# Arc.net
KiCad netlist of a schematic drawn in Altium Designer
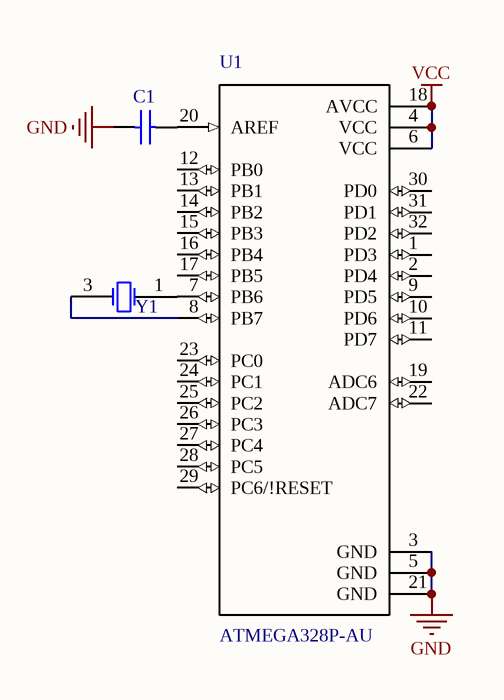
[diagram p0: Arc.SchDoc]

(export (version "E")
  (design (tool "Eeschema 10.0.6"))
  (components
    (comp (ref "C1")
      (value "100nF (104) 10% 16V")
      (footprint "0402_C")
      (description "贴片电容")
      (libsource (lib "Miscellaneous Devices LC") (part "0402 100nF (104) 10% 16V"))
    )
    (comp (ref "U1")
      (value "ATMEGA328P-AU")
      (footprint "*QFP80P900X900X120-32N")
      (description "Microcontroller Mcu, 8 Bit, Atmega, 20mhz, Tqfp-32")
      (fields (field (name "MF") "Microchip"))
      (libsource (lib "altium-import") (part "root_0_ATMEGA328P-AU_"))
    )
    (comp (ref "Y1")
      (value "16MHZ 9PF 10PPM")
      (footprint "SMD-3225_4P")
      (description "贴片晶振")
      (libsource (lib "Miscellaneous Devices LC") (part "SMD-3225_4P  16MHZ 9PF 10PPM"))
    )
  )
  (nets
    (net (code "1") (name "GND") (class "Default")
      (node (ref "C1") (pin "1") (pinfunction "1_1") (pintype "passive"))
      (node (ref "U1") (pin "21") (pinfunction "GND_21") (pintype "power_in"))
      (node (ref "U1") (pin "3") (pinfunction "GND_3") (pintype "power_in"))
      (node (ref "U1") (pin "5") (pinfunction "GND_5") (pintype "power_in"))
    )
    (net (code "2") (name "Net-(U1-AREF)") (class "Default")
      (node (ref "C1") (pin "2") (pinfunction "2_2") (pintype "passive"))
      (node (ref "U1") (pin "20") (pinfunction "AREF_20") (pintype "input"))
    )
    (net (code "3") (name "Net-(U1-PB6)") (class "Default")
      (node (ref "U1") (pin "7") (pinfunction "PB6_7") (pintype "bidirectional"))
      (node (ref "Y1") (pin "1") (pinfunction "OSC1_1") (pintype "passive"))
    )
    (net (code "4") (name "Net-(U1-PB7)") (class "Default")
      (node (ref "U1") (pin "8") (pinfunction "PB7_8") (pintype "bidirectional"))
      (node (ref "Y1") (pin "3") (pinfunction "OSC2_3") (pintype "passive"))
    )
    (net (code "5") (name "VCC") (class "Default")
      (node (ref "U1") (pin "18") (pinfunction "AVCC_18") (pintype "power_in"))
      (node (ref "U1") (pin "4") (pinfunction "VCC_4") (pintype "power_in"))
      (node (ref "U1") (pin "6") (pinfunction "VCC_6") (pintype "power_in"))
    )
    (net (code "6") (name "unconnected-(U1-ADC6-Pad19)") (class "Default")
      (node (ref "U1") (pin "19") (pinfunction "ADC6_19") (pintype "bidirectional"))
    )
    (net (code "7") (name "unconnected-(U1-ADC7-Pad22)") (class "Default")
      (node (ref "U1") (pin "22") (pinfunction "ADC7_22") (pintype "bidirectional"))
    )
    (net (code "8") (name "unconnected-(U1-PB0-Pad12)") (class "Default")
      (node (ref "U1") (pin "12") (pinfunction "PB0_12") (pintype "bidirectional"))
    )
    (net (code "9") (name "unconnected-(U1-PB1-Pad13)") (class "Default")
      (node (ref "U1") (pin "13") (pinfunction "PB1_13") (pintype "bidirectional"))
    )
    (net (code "10") (name "unconnected-(U1-PB2-Pad14)") (class "Default")
      (node (ref "U1") (pin "14") (pinfunction "PB2_14") (pintype "bidirectional"))
    )
    (net (code "11") (name "unconnected-(U1-PB3-Pad15)") (class "Default")
      (node (ref "U1") (pin "15") (pinfunction "PB3_15") (pintype "bidirectional"))
    )
    (net (code "12") (name "unconnected-(U1-PB4-Pad16)") (class "Default")
      (node (ref "U1") (pin "16") (pinfunction "PB4_16") (pintype "bidirectional"))
    )
    (net (code "13") (name "unconnected-(U1-PB5-Pad17)") (class "Default")
      (node (ref "U1") (pin "17") (pinfunction "PB5_17") (pintype "bidirectional"))
    )
    (net (code "14") (name "unconnected-(U1-PC0-Pad23)") (class "Default")
      (node (ref "U1") (pin "23") (pinfunction "PC0_23") (pintype "bidirectional"))
    )
    (net (code "15") (name "unconnected-(U1-PC1-Pad24)") (class "Default")
      (node (ref "U1") (pin "24") (pinfunction "PC1_24") (pintype "bidirectional"))
    )
    (net (code "16") (name "unconnected-(U1-PC2-Pad25)") (class "Default")
      (node (ref "U1") (pin "25") (pinfunction "PC2_25") (pintype "bidirectional"))
    )
    (net (code "17") (name "unconnected-(U1-PC3-Pad26)") (class "Default")
      (node (ref "U1") (pin "26") (pinfunction "PC3_26") (pintype "bidirectional"))
    )
    (net (code "18") (name "unconnected-(U1-PC4-Pad27)") (class "Default")
      (node (ref "U1") (pin "27") (pinfunction "PC4_27") (pintype "bidirectional"))
    )
    (net (code "19") (name "unconnected-(U1-PC5-Pad28)") (class "Default")
      (node (ref "U1") (pin "28") (pinfunction "PC5_28") (pintype "bidirectional"))
    )
    (net (code "20") (name "unconnected-(U1-PC6{slash}!RESET-Pad29)") (class "Default")
      (node (ref "U1") (pin "29") (pinfunction "PC6/!RESET_29") (pintype "bidirectional"))
    )
    (net (code "21") (name "unconnected-(U1-PD0-Pad30)") (class "Default")
      (node (ref "U1") (pin "30") (pinfunction "PD0_30") (pintype "bidirectional"))
    )
    (net (code "22") (name "unconnected-(U1-PD1-Pad31)") (class "Default")
      (node (ref "U1") (pin "31") (pinfunction "PD1_31") (pintype "bidirectional"))
    )
    (net (code "23") (name "unconnected-(U1-PD2-Pad32)") (class "Default")
      (node (ref "U1") (pin "32") (pinfunction "PD2_32") (pintype "bidirectional"))
    )
    (net (code "24") (name "unconnected-(U1-PD3-Pad1)") (class "Default")
      (node (ref "U1") (pin "1") (pinfunction "PD3_1") (pintype "bidirectional"))
    )
    (net (code "25") (name "unconnected-(U1-PD4-Pad2)") (class "Default")
      (node (ref "U1") (pin "2") (pinfunction "PD4_2") (pintype "bidirectional"))
    )
    (net (code "26") (name "unconnected-(U1-PD5-Pad9)") (class "Default")
      (node (ref "U1") (pin "9") (pinfunction "PD5_9") (pintype "bidirectional"))
    )
    (net (code "27") (name "unconnected-(U1-PD6-Pad10)") (class "Default")
      (node (ref "U1") (pin "10") (pinfunction "PD6_10") (pintype "bidirectional"))
    )
    (net (code "28") (name "unconnected-(U1-PD7-Pad11)") (class "Default")
      (node (ref "U1") (pin "11") (pinfunction "PD7_11") (pintype "bidirectional"))
    )
  )
)
